# IV_Swinger_2_ss_mod.net
KiCad netlist of a schematic drawn in EAGLE
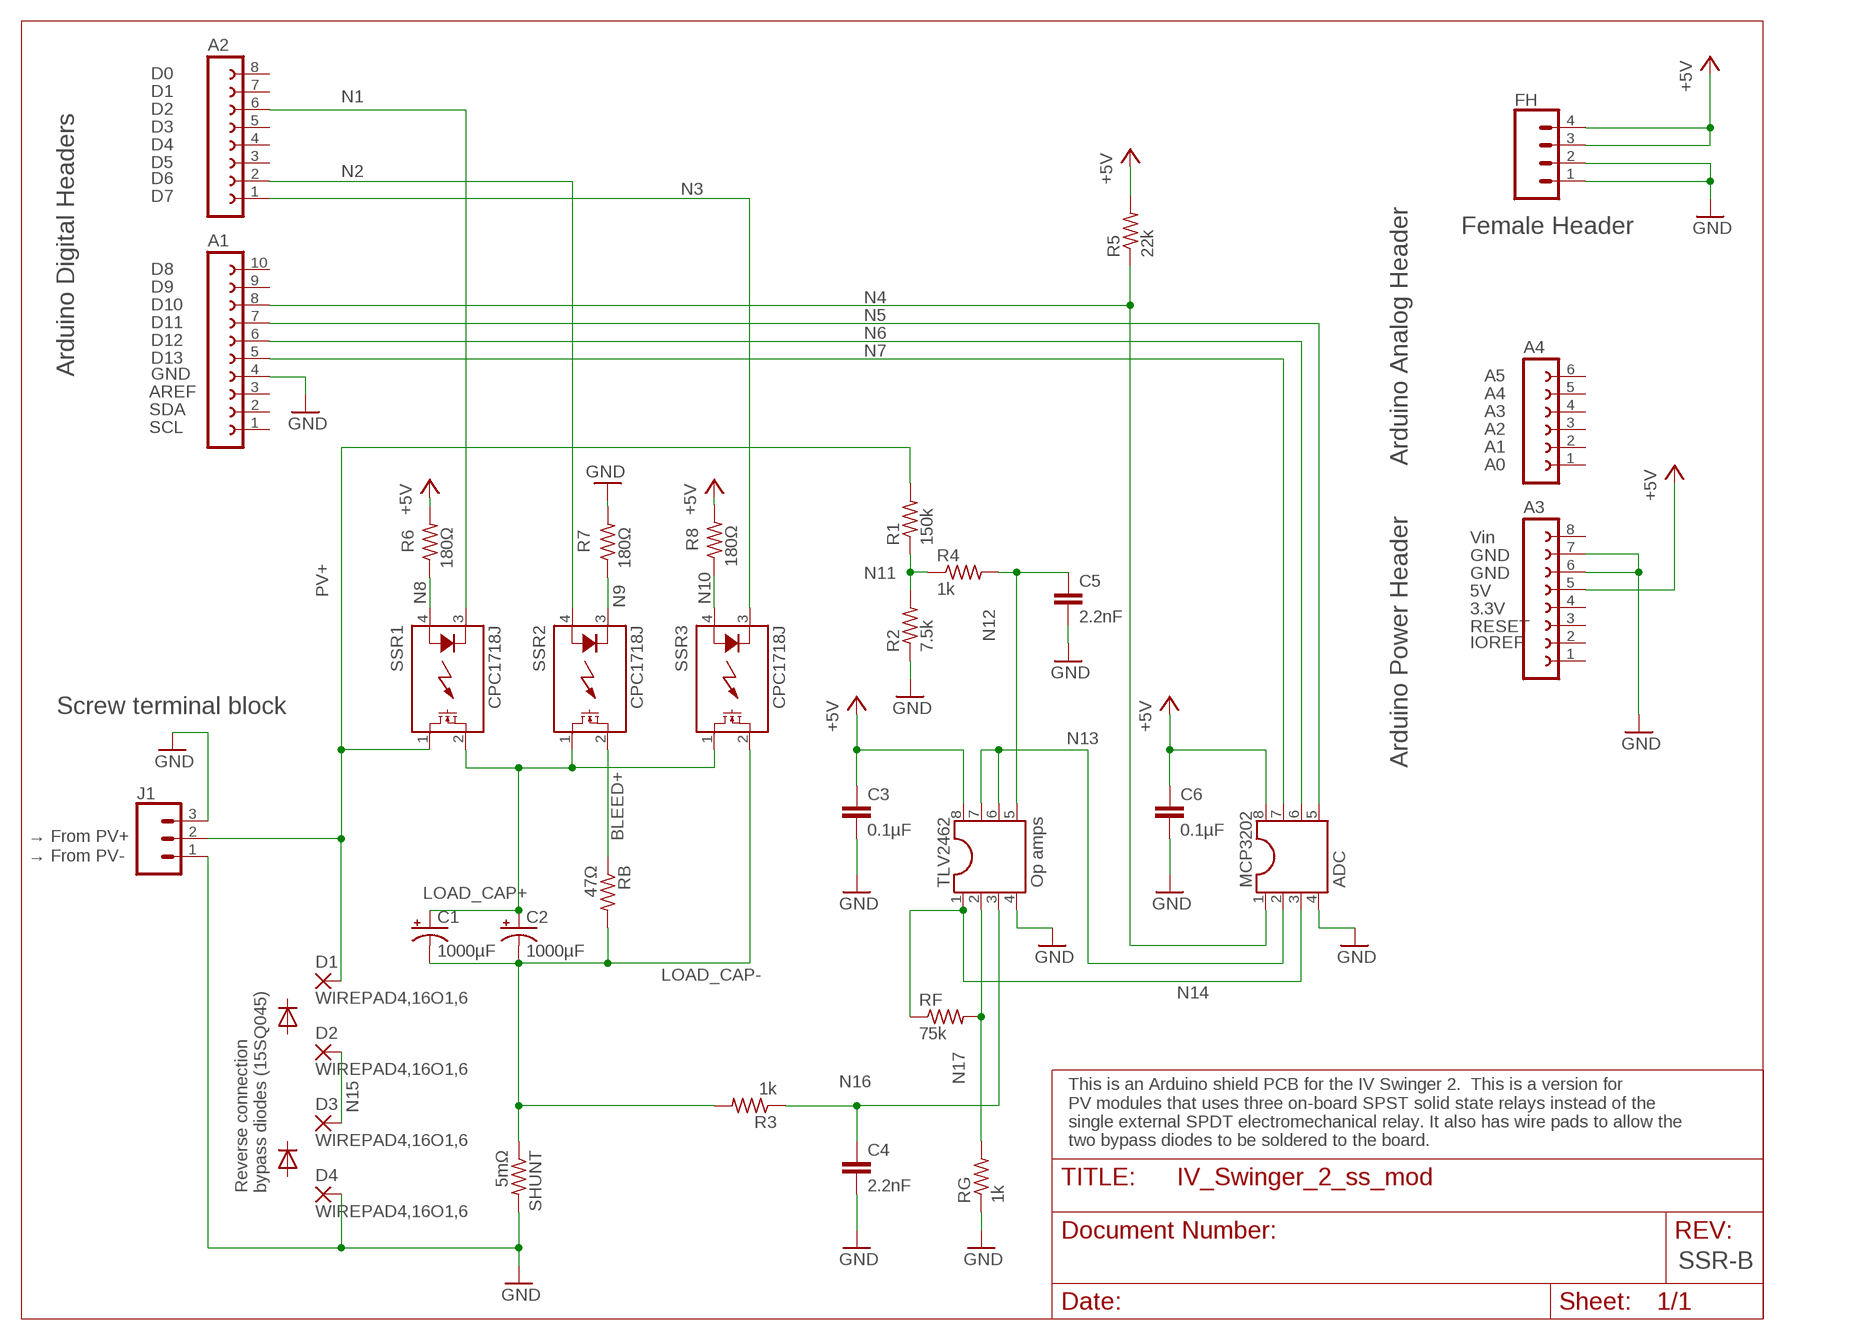
[diagram p0: schematic, sheet 1]

(export (version "E")
  (design (tool "Eeschema 10.0.6"))
  (components
    (comp (ref "A1")
      (value "FE10-1")
      (footprint "eagle-import:FE10")
      (libsource (lib "eagle-import") (part "FE10-1"))
    )
    (comp (ref "A2")
      (value "FE08-1")
      (footprint "eagle-import:FE08")
      (libsource (lib "eagle-import") (part "FE08-1"))
    )
    (comp (ref "A3")
      (value "FE08-1")
      (footprint "eagle-import:FE08")
      (libsource (lib "eagle-import") (part "FE08-1"))
    )
    (comp (ref "A4")
      (value "FE06-1")
      (footprint "eagle-import:FE06")
      (libsource (lib "eagle-import") (part "FE06-1"))
    )
    (comp (ref "C1")
      (value "1000µF")
      (footprint "eagle-import:E7,5-18")
      (libsource (lib "eagle-import") (part "CPOL-USE7.5-18"))
    )
    (comp (ref "C2")
      (value "1000µF")
      (footprint "eagle-import:E7,5-18")
      (libsource (lib "eagle-import") (part "CPOL-USE7.5-18"))
    )
    (comp (ref "C3")
      (value "0.1µF")
      (footprint "eagle-import:C025-030X050")
      (libsource (lib "eagle-import") (part "C-EU025-030X050"))
    )
    (comp (ref "C4")
      (value "2.2nF")
      (footprint "eagle-import:C025-030X050")
      (libsource (lib "eagle-import") (part "C-EU025-030X050"))
    )
    (comp (ref "C5")
      (value "2.2nF")
      (footprint "eagle-import:C025-030X050")
      (libsource (lib "eagle-import") (part "C-EU025-030X050"))
    )
    (comp (ref "C6")
      (value "0.1µF")
      (footprint "eagle-import:C025-030X050")
      (libsource (lib "eagle-import") (part "C-EU025-030X050"))
    )
    (comp (ref "D1")
      (value "WIREPAD4,16O1,6")
      (footprint "eagle-import:4,16O1,6")
      (fields (field (name "SPICEPREFIX") "X"))
      (libsource (lib "eagle-import") (part "WIREPAD4,16O1,6"))
    )
    (comp (ref "D2")
      (value "WIREPAD4,16O1,6")
      (footprint "eagle-import:4,16O1,6")
      (libsource (lib "eagle-import") (part "WIREPAD4,16O1,6"))
    )
    (comp (ref "D3")
      (value "WIREPAD4,16O1,6")
      (footprint "eagle-import:4,16O1,6")
      (libsource (lib "eagle-import") (part "WIREPAD4,16O1,6"))
    )
    (comp (ref "D4")
      (value "WIREPAD4,16O1,6")
      (footprint "eagle-import:4,16O1,6")
      (libsource (lib "eagle-import") (part "WIREPAD4,16O1,6"))
    )
    (comp (ref "FH")
      (value "CONN_04LONGPADS")
      (footprint "eagle-import:1X04_LONGPADS")
      (libsource (lib "eagle-import") (part "CONN_04LONGPADS"))
    )
    (comp (ref "J1")
      (value "CONN_03-SCREW-5MM")
      (footprint "eagle-import:SCREWTERMINAL-5MM-3")
      (libsource (lib "eagle-import") (part "CONN_03-SCREW-5MM"))
    )
    (comp (ref "MCP3202")
      (value "ADC")
      (footprint "eagle-import:SOCKET-08")
      (libsource (lib "eagle-import") (part "DIL8S"))
    )
    (comp (ref "R1")
      (value "150k")
      (footprint "eagle-import:0207_10")
      (libsource (lib "eagle-import") (part "R-US_0207/10"))
    )
    (comp (ref "R2")
      (value "7.5k")
      (footprint "eagle-import:0207_10")
      (libsource (lib "eagle-import") (part "R-US_0207/10"))
    )
    (comp (ref "R3")
      (value "1k")
      (footprint "eagle-import:0207_10")
      (libsource (lib "eagle-import") (part "R-US_0207/10"))
    )
    (comp (ref "R4")
      (value "1k")
      (footprint "eagle-import:0207_10")
      (libsource (lib "eagle-import") (part "R-US_0207/10"))
    )
    (comp (ref "R5")
      (value "22k")
      (footprint "eagle-import:0207_10")
      (libsource (lib "eagle-import") (part "R-US_0207/10"))
    )
    (comp (ref "R6")
      (value "180Ω")
      (footprint "eagle-import:0207_10")
      (libsource (lib "eagle-import") (part "R-US_0207/10"))
    )
    (comp (ref "R7")
      (value "180Ω")
      (footprint "eagle-import:0207_10")
      (libsource (lib "eagle-import") (part "R-US_0207/10"))
    )
    (comp (ref "R8")
      (value "180Ω")
      (footprint "eagle-import:0207_10")
      (libsource (lib "eagle-import") (part "R-US_0207/10"))
    )
    (comp (ref "RB")
      (value "47Ω")
      (footprint "eagle-import:P0817V")
      (libsource (lib "eagle-import") (part "R-US_0817/7V"))
    )
    (comp (ref "RF")
      (value "75k")
      (footprint "eagle-import:0207_10")
      (libsource (lib "eagle-import") (part "R-US_0207/10"))
    )
    (comp (ref "RG")
      (value "1k")
      (footprint "eagle-import:0207_10")
      (libsource (lib "eagle-import") (part "R-US_0207/10"))
    )
    (comp (ref "SHUNT")
      (value "5mΩ")
      (footprint "eagle-import:0617V")
      (libsource (lib "eagle-import") (part "R-US_0617/5V"))
    )
    (comp (ref "SSR1")
      (value "CPC1718J")
      (footprint "eagle-import:I4-PAC")
      (libsource (lib "eagle-import") (part "CPC1718J"))
    )
    (comp (ref "SSR2")
      (value "CPC1718J")
      (footprint "eagle-import:I4-PAC")
      (libsource (lib "eagle-import") (part "CPC1718J"))
    )
    (comp (ref "SSR3")
      (value "CPC1718J")
      (footprint "eagle-import:I4-PAC")
      (libsource (lib "eagle-import") (part "CPC1718J"))
    )
    (comp (ref "TLV2462")
      (value "Op amps")
      (footprint "eagle-import:SOCKET-08")
      (libsource (lib "eagle-import") (part "DIL8S"))
    )
  )
  (nets
    (net (code "1") (name "+5V") (class "Default")
      (node (ref "A3") (pin "5") (pinfunction "5_5") (pintype "passive"))
      (node (ref "C3") (pin "1") (pinfunction "1_1") (pintype "passive"))
      (node (ref "C6") (pin "1") (pinfunction "1_1") (pintype "passive"))
      (node (ref "FH") (pin "3") (pinfunction "3_3") (pintype "passive"))
      (node (ref "FH") (pin "4") (pinfunction "4_4") (pintype "passive"))
      (node (ref "MCP3202") (pin "8") (pinfunction "8_8") (pintype "passive"))
      (node (ref "R5") (pin "2") (pinfunction "2_2") (pintype "passive"))
      (node (ref "R6") (pin "2") (pinfunction "2_2") (pintype "passive"))
      (node (ref "R8") (pin "2") (pinfunction "2_2") (pintype "passive"))
      (node (ref "TLV2462") (pin "8") (pinfunction "8_8") (pintype "passive"))
    )
    (net (code "2") (name "/BLEED+") (class "Default")
      (node (ref "RB") (pin "1") (pinfunction "1_1") (pintype "passive"))
      (node (ref "SSR2") (pin "2") (pinfunction "DS2_2") (pintype "passive"))
    )
    (net (code "3") (name "/LOAD_CAP+") (class "Default")
      (node (ref "C1") (pin "+") (pinfunction "+_+") (pintype "passive"))
      (node (ref "C2") (pin "+") (pinfunction "+_+") (pintype "passive"))
      (node (ref "SSR1") (pin "2") (pinfunction "DS2_2") (pintype "passive"))
      (node (ref "SSR2") (pin "1") (pinfunction "DS1_1") (pintype "passive"))
      (node (ref "SSR3") (pin "1") (pinfunction "DS1_1") (pintype "passive"))
    )
    (net (code "4") (name "/LOAD_CAP-") (class "Default")
      (node (ref "C1") (pin "-") (pinfunction "-_-") (pintype "passive"))
      (node (ref "C2") (pin "-") (pinfunction "-_-") (pintype "passive"))
      (node (ref "R3") (pin "2") (pinfunction "2_2") (pintype "passive"))
      (node (ref "RB") (pin "2") (pinfunction "2_2") (pintype "passive"))
      (node (ref "SHUNT") (pin "1") (pinfunction "1_1") (pintype "passive"))
      (node (ref "SSR3") (pin "2") (pinfunction "DS2_2") (pintype "passive"))
    )
    (net (code "5") (name "/N1") (class "Default")
      (node (ref "A2") (pin "6") (pinfunction "6_6") (pintype "passive"))
      (node (ref "SSR1") (pin "3") (pinfunction "K_3") (pintype "passive"))
    )
    (net (code "6") (name "/N2") (class "Default")
      (node (ref "A2") (pin "2") (pinfunction "2_2") (pintype "passive"))
      (node (ref "SSR2") (pin "4") (pinfunction "A_4") (pintype "passive"))
    )
    (net (code "7") (name "/N3") (class "Default")
      (node (ref "A2") (pin "1") (pinfunction "1_1") (pintype "passive"))
      (node (ref "SSR3") (pin "3") (pinfunction "K_3") (pintype "passive"))
    )
    (net (code "8") (name "/N4") (class "Default")
      (node (ref "A1") (pin "8") (pinfunction "8_8") (pintype "passive"))
      (node (ref "MCP3202") (pin "1") (pinfunction "1_1") (pintype "passive"))
      (node (ref "R5") (pin "1") (pinfunction "1_1") (pintype "passive"))
    )
    (net (code "9") (name "/N5") (class "Default")
      (node (ref "A1") (pin "7") (pinfunction "7_7") (pintype "passive"))
      (node (ref "MCP3202") (pin "5") (pinfunction "5_5") (pintype "passive"))
    )
    (net (code "10") (name "/N6") (class "Default")
      (node (ref "A1") (pin "6") (pinfunction "6_6") (pintype "passive"))
      (node (ref "MCP3202") (pin "6") (pinfunction "6_6") (pintype "passive"))
    )
    (net (code "11") (name "/N7") (class "Default")
      (node (ref "A1") (pin "5") (pinfunction "5_5") (pintype "passive"))
      (node (ref "MCP3202") (pin "7") (pinfunction "7_7") (pintype "passive"))
    )
    (net (code "12") (name "/N8") (class "Default")
      (node (ref "R6") (pin "1") (pinfunction "1_1") (pintype "passive"))
      (node (ref "SSR1") (pin "4") (pinfunction "A_4") (pintype "passive"))
    )
    (net (code "13") (name "/N9") (class "Default")
      (node (ref "R7") (pin "1") (pinfunction "1_1") (pintype "passive"))
      (node (ref "SSR2") (pin "3") (pinfunction "K_3") (pintype "passive"))
    )
    (net (code "14") (name "/N10") (class "Default")
      (node (ref "R8") (pin "1") (pinfunction "1_1") (pintype "passive"))
      (node (ref "SSR3") (pin "4") (pinfunction "A_4") (pintype "passive"))
    )
    (net (code "15") (name "/N11") (class "Default")
      (node (ref "R1") (pin "1") (pinfunction "1_1") (pintype "passive"))
      (node (ref "R2") (pin "2") (pinfunction "2_2") (pintype "passive"))
      (node (ref "R4") (pin "1") (pinfunction "1_1") (pintype "passive"))
    )
    (net (code "16") (name "/N12") (class "Default")
      (node (ref "C5") (pin "1") (pinfunction "1_1") (pintype "passive"))
      (node (ref "R4") (pin "2") (pinfunction "2_2") (pintype "passive"))
      (node (ref "TLV2462") (pin "5") (pinfunction "5_5") (pintype "passive"))
    )
    (net (code "17") (name "/N13") (class "Default")
      (node (ref "MCP3202") (pin "2") (pinfunction "2_2") (pintype "passive"))
      (node (ref "TLV2462") (pin "6") (pinfunction "6_6") (pintype "passive"))
      (node (ref "TLV2462") (pin "7") (pinfunction "7_7") (pintype "passive"))
    )
    (net (code "18") (name "/N14") (class "Default")
      (node (ref "MCP3202") (pin "3") (pinfunction "3_3") (pintype "passive"))
      (node (ref "RF") (pin "1") (pinfunction "1_1") (pintype "passive"))
      (node (ref "TLV2462") (pin "1") (pinfunction "1_1") (pintype "passive"))
    )
    (net (code "19") (name "/N15") (class "Default")
      (node (ref "D2") (pin "1") (pinfunction "P_1") (pintype "passive"))
      (node (ref "D3") (pin "1") (pinfunction "P_1") (pintype "passive"))
    )
    (net (code "20") (name "/N16") (class "Default")
      (node (ref "C4") (pin "1") (pinfunction "1_1") (pintype "passive"))
      (node (ref "R3") (pin "1") (pinfunction "1_1") (pintype "passive"))
      (node (ref "TLV2462") (pin "3") (pinfunction "3_3") (pintype "passive"))
    )
    (net (code "21") (name "/N17") (class "Default")
      (node (ref "RF") (pin "2") (pinfunction "2_2") (pintype "passive"))
      (node (ref "RG") (pin "2") (pinfunction "2_2") (pintype "passive"))
      (node (ref "TLV2462") (pin "2") (pinfunction "2_2") (pintype "passive"))
    )
    (net (code "22") (name "/PV+") (class "Default")
      (node (ref "D1") (pin "1") (pinfunction "P_1") (pintype "passive"))
      (node (ref "J1") (pin "2") (pinfunction "2_2") (pintype "passive"))
      (node (ref "R1") (pin "2") (pinfunction "2_2") (pintype "passive"))
      (node (ref "SSR1") (pin "1") (pinfunction "DS1_1") (pintype "passive"))
    )
    (net (code "23") (name "GND") (class "Default")
      (node (ref "A1") (pin "4") (pinfunction "4_4") (pintype "passive"))
      (node (ref "A3") (pin "6") (pinfunction "6_6") (pintype "passive"))
      (node (ref "A3") (pin "7") (pinfunction "7_7") (pintype "passive"))
      (node (ref "C3") (pin "2") (pinfunction "2_2") (pintype "passive"))
      (node (ref "C4") (pin "2") (pinfunction "2_2") (pintype "passive"))
      (node (ref "C5") (pin "2") (pinfunction "2_2") (pintype "passive"))
      (node (ref "C6") (pin "2") (pinfunction "2_2") (pintype "passive"))
      (node (ref "D4") (pin "1") (pinfunction "P_1") (pintype "passive"))
      (node (ref "FH") (pin "1") (pinfunction "1_1") (pintype "passive"))
      (node (ref "FH") (pin "2") (pinfunction "2_2") (pintype "passive"))
      (node (ref "J1") (pin "1") (pinfunction "1_1") (pintype "passive"))
      (node (ref "J1") (pin "3") (pinfunction "3_3") (pintype "passive"))
      (node (ref "MCP3202") (pin "4") (pinfunction "4_4") (pintype "passive"))
      (node (ref "R2") (pin "1") (pinfunction "1_1") (pintype "passive"))
      (node (ref "R7") (pin "2") (pinfunction "2_2") (pintype "passive"))
      (node (ref "RG") (pin "1") (pinfunction "1_1") (pintype "passive"))
      (node (ref "SHUNT") (pin "2") (pinfunction "2_2") (pintype "passive"))
      (node (ref "TLV2462") (pin "4") (pinfunction "4_4") (pintype "passive"))
    )
    (net (code "24") (name "unconnected-(A1-Pad1)") (class "Default")
      (node (ref "A1") (pin "1") (pinfunction "1_1") (pintype "passive"))
    )
    (net (code "25") (name "unconnected-(A1-Pad2)") (class "Default")
      (node (ref "A1") (pin "2") (pinfunction "2_2") (pintype "passive"))
    )
    (net (code "26") (name "unconnected-(A1-Pad3)") (class "Default")
      (node (ref "A1") (pin "3") (pinfunction "3_3") (pintype "passive"))
    )
    (net (code "27") (name "unconnected-(A1-Pad9)") (class "Default")
      (node (ref "A1") (pin "9") (pinfunction "9_9") (pintype "passive"))
    )
    (net (code "28") (name "unconnected-(A1-Pad10)") (class "Default")
      (node (ref "A1") (pin "10") (pinfunction "10_10") (pintype "passive"))
    )
    (net (code "29") (name "unconnected-(A2-Pad3)") (class "Default")
      (node (ref "A2") (pin "3") (pinfunction "3_3") (pintype "passive"))
    )
    (net (code "30") (name "unconnected-(A2-Pad4)") (class "Default")
      (node (ref "A2") (pin "4") (pinfunction "4_4") (pintype "passive"))
    )
    (net (code "31") (name "unconnected-(A2-Pad5)") (class "Default")
      (node (ref "A2") (pin "5") (pinfunction "5_5") (pintype "passive"))
    )
    (net (code "32") (name "unconnected-(A2-Pad7)") (class "Default")
      (node (ref "A2") (pin "7") (pinfunction "7_7") (pintype "passive"))
    )
    (net (code "33") (name "unconnected-(A2-Pad8)") (class "Default")
      (node (ref "A2") (pin "8") (pinfunction "8_8") (pintype "passive"))
    )
    (net (code "34") (name "unconnected-(A3-Pad1)") (class "Default")
      (node (ref "A3") (pin "1") (pinfunction "1_1") (pintype "passive"))
    )
    (net (code "35") (name "unconnected-(A3-Pad2)") (class "Default")
      (node (ref "A3") (pin "2") (pinfunction "2_2") (pintype "passive"))
    )
    (net (code "36") (name "unconnected-(A3-Pad3)") (class "Default")
      (node (ref "A3") (pin "3") (pinfunction "3_3") (pintype "passive"))
    )
    (net (code "37") (name "unconnected-(A3-Pad4)") (class "Default")
      (node (ref "A3") (pin "4") (pinfunction "4_4") (pintype "passive"))
    )
    (net (code "38") (name "unconnected-(A3-Pad8)") (class "Default")
      (node (ref "A3") (pin "8") (pinfunction "8_8") (pintype "passive"))
    )
    (net (code "39") (name "unconnected-(A4-Pad1)") (class "Default")
      (node (ref "A4") (pin "1") (pinfunction "1_1") (pintype "passive"))
    )
    (net (code "40") (name "unconnected-(A4-Pad2)") (class "Default")
      (node (ref "A4") (pin "2") (pinfunction "2_2") (pintype "passive"))
    )
    (net (code "41") (name "unconnected-(A4-Pad3)") (class "Default")
      (node (ref "A4") (pin "3") (pinfunction "3_3") (pintype "passive"))
    )
    (net (code "42") (name "unconnected-(A4-Pad4)") (class "Default")
      (node (ref "A4") (pin "4") (pinfunction "4_4") (pintype "passive"))
    )
    (net (code "43") (name "unconnected-(A4-Pad5)") (class "Default")
      (node (ref "A4") (pin "5") (pinfunction "5_5") (pintype "passive"))
    )
    (net (code "44") (name "unconnected-(A4-Pad6)") (class "Default")
      (node (ref "A4") (pin "6") (pinfunction "6_6") (pintype "passive"))
    )
  )
)
